# oneButton.net
KiCad netlist of a schematic drawn in Altium Designer
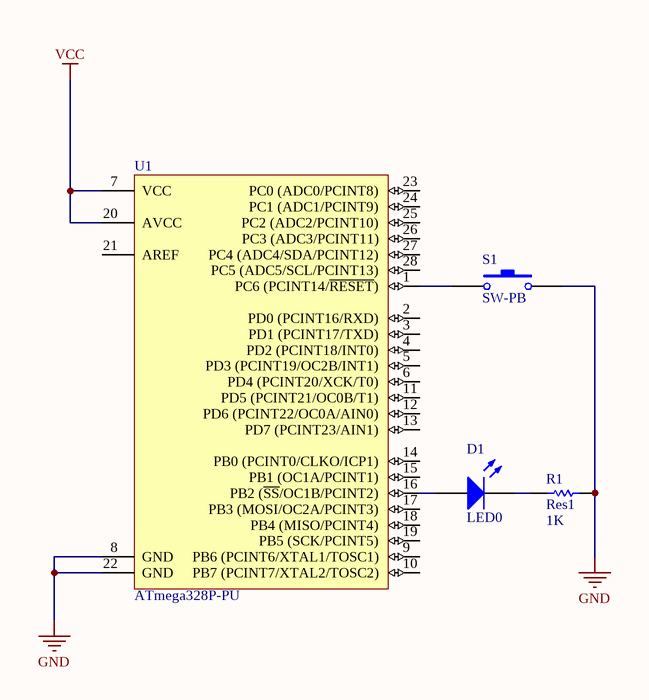
[diagram p0: oneButton.SchDoc]

(export (version "E")
  (design (tool "Eeschema 10.0.6"))
  (components
    (comp (ref "D1")
      (value "LED0")
      (footprint "LED-0")
      (description "Typical INFRARED GaAs LED")
      (fields (field (name "PUBLISHER") "Altium Limited"))
      (libsource (lib "Miscellaneous Devices") (part "LED0"))
    )
    (comp (ref "R1")
      (value "Res1")
      (footprint "AXIAL-0.3")
      (description "Resistor")
      (fields (field (name "ALTIUM_VALUE") "1K") (field (name "PUBLISHER") "Altium Limited"))
      (libsource (lib "Miscellaneous Devices") (part "Res1"))
    )
    (comp (ref "S1")
      (value "SW-PB")
      (footprint "SPST-2")
      (description "Switch")
      (fields (field (name "PUBLISHER") "Altium Limited"))
      (libsource (lib "Miscellaneous Devices") (part "SW-PB"))
    )
    (comp (ref "U1")
      (value "ATmega328P-PU")
      (footprint "28P3")
      (fields (field (name "PUBLISHER") "Altium Limited"))
      (libsource (lib "Atmel Microcontroller 8-Bit megaAVR") (part "ATmega328P-PU"))
    )
  )
  (nets
    (net (code "1") (name "GND") (class "Default")
      (node (ref "R1") (pin "2") (pinfunction "2_2") (pintype "passive"))
      (node (ref "S1") (pin "2") (pinfunction "2_2") (pintype "passive"))
      (node (ref "U1") (pin "22") (pinfunction "GND_22") (pintype "power_in"))
      (node (ref "U1") (pin "8") (pinfunction "GND_8") (pintype "power_in"))
    )
    (net (code "2") (name "Net-(D1-A)") (class "Default")
      (node (ref "D1") (pin "1") (pinfunction "A_1") (pintype "passive"))
      (node (ref "U1") (pin "16") (pinfunction "PB2_(~{SS}/OC1B/PCINT2)_16") (pintype "bidirectional"))
    )
    (net (code "3") (name "Net-(D1-K)") (class "Default")
      (node (ref "D1") (pin "2") (pinfunction "K_2") (pintype "passive"))
      (node (ref "R1") (pin "1") (pinfunction "1_1") (pintype "passive"))
    )
    (net (code "4") (name "Net-(U1-PC6_(PCINT14{slash}~{RESET}))") (class "Default")
      (node (ref "S1") (pin "1") (pinfunction "1_1") (pintype "passive"))
      (node (ref "U1") (pin "1") (pinfunction "PC6_(PCINT14/~{RESET})_1") (pintype "bidirectional"))
    )
    (net (code "5") (name "VCC") (class "Default")
      (node (ref "U1") (pin "20") (pinfunction "AVCC_20") (pintype "power_in"))
      (node (ref "U1") (pin "7") (pinfunction "VCC_7") (pintype "power_in"))
    )
    (net (code "6") (name "unconnected-(U1-AREF-Pad21)") (class "Default")
      (node (ref "U1") (pin "21") (pinfunction "AREF_21") (pintype "power_in"))
    )
    (net (code "7") (name "unconnected-(U1-PB0_(PCINT0{slash}CLKO{slash}ICP1)-Pad14)") (class "Default")
      (node (ref "U1") (pin "14") (pinfunction "PB0_(PCINT0/CLKO/ICP1)_14") (pintype "bidirectional"))
    )
    (net (code "8") (name "unconnected-(U1-PB1_(OC1A{slash}PCINT1)-Pad15)") (class "Default")
      (node (ref "U1") (pin "15") (pinfunction "PB1_(OC1A/PCINT1)_15") (pintype "bidirectional"))
    )
    (net (code "9") (name "unconnected-(U1-PB3_(MOSI{slash}OC2A{slash}PCINT3)-Pad17)") (class "Default")
      (node (ref "U1") (pin "17") (pinfunction "PB3_(MOSI/OC2A/PCINT3)_17") (pintype "bidirectional"))
    )
    (net (code "10") (name "unconnected-(U1-PB4_(MISO{slash}PCINT4)-Pad18)") (class "Default")
      (node (ref "U1") (pin "18") (pinfunction "PB4_(MISO/PCINT4)_18") (pintype "bidirectional"))
    )
    (net (code "11") (name "unconnected-(U1-PB5_(SCK{slash}PCINT5)-Pad19)") (class "Default")
      (node (ref "U1") (pin "19") (pinfunction "PB5_(SCK/PCINT5)_19") (pintype "bidirectional"))
    )
    (net (code "12") (name "unconnected-(U1-PB6_(PCINT6{slash}XTAL1{slash}TOSC1)-Pad9)") (class "Default")
      (node (ref "U1") (pin "9") (pinfunction "PB6_(PCINT6/XTAL1/TOSC1)_9") (pintype "bidirectional"))
    )
    (net (code "13") (name "unconnected-(U1-PB7_(PCINT7{slash}XTAL2{slash}TOSC2)-Pad10)") (class "Default")
      (node (ref "U1") (pin "10") (pinfunction "PB7_(PCINT7/XTAL2/TOSC2)_10") (pintype "bidirectional"))
    )
    (net (code "14") (name "unconnected-(U1-PC0_(ADC0{slash}PCINT8)-Pad23)") (class "Default")
      (node (ref "U1") (pin "23") (pinfunction "PC0_(ADC0/PCINT8)_23") (pintype "bidirectional"))
    )
    (net (code "15") (name "unconnected-(U1-PC1_(ADC1{slash}PCINT9)-Pad24)") (class "Default")
      (node (ref "U1") (pin "24") (pinfunction "PC1_(ADC1/PCINT9)_24") (pintype "bidirectional"))
    )
    (net (code "16") (name "unconnected-(U1-PC2_(ADC2{slash}PCINT10)-Pad25)") (class "Default")
      (node (ref "U1") (pin "25") (pinfunction "PC2_(ADC2/PCINT10)_25") (pintype "bidirectional"))
    )
    (net (code "17") (name "unconnected-(U1-PC3_(ADC3{slash}PCINT11)-Pad26)") (class "Default")
      (node (ref "U1") (pin "26") (pinfunction "PC3_(ADC3/PCINT11)_26") (pintype "bidirectional"))
    )
    (net (code "18") (name "unconnected-(U1-PC4_(ADC4{slash}SDA{slash}PCINT12)-Pad27)") (class "Default")
      (node (ref "U1") (pin "27") (pinfunction "PC4_(ADC4/SDA/PCINT12)_27") (pintype "bidirectional"))
    )
    (net (code "19") (name "unconnected-(U1-PC5_(ADC5{slash}SCL{slash}PCINT13)-Pad28)") (class "Default")
      (node (ref "U1") (pin "28") (pinfunction "PC5_(ADC5/SCL/PCINT13)_28") (pintype "bidirectional"))
    )
    (net (code "20") (name "unconnected-(U1-PD0_(PCINT16{slash}RXD)-Pad2)") (class "Default")
      (node (ref "U1") (pin "2") (pinfunction "PD0_(PCINT16/RXD)_2") (pintype "bidirectional"))
    )
    (net (code "21") (name "unconnected-(U1-PD1_(PCINT17{slash}TXD)-Pad3)") (class "Default")
      (node (ref "U1") (pin "3") (pinfunction "PD1_(PCINT17/TXD)_3") (pintype "bidirectional"))
    )
    (net (code "22") (name "unconnected-(U1-PD2_(PCINT18{slash}INT0)-Pad4)") (class "Default")
      (node (ref "U1") (pin "4") (pinfunction "PD2_(PCINT18/INT0)_4") (pintype "bidirectional"))
    )
    (net (code "23") (name "unconnected-(U1-PD3_(PCINT19{slash}OC2B{slash}INT1)-Pad5)") (class "Default")
      (node (ref "U1") (pin "5") (pinfunction "PD3_(PCINT19/OC2B/INT1)_5") (pintype "bidirectional"))
    )
    (net (code "24") (name "unconnected-(U1-PD4_(PCINT20{slash}XCK{slash}T0)-Pad6)") (class "Default")
      (node (ref "U1") (pin "6") (pinfunction "PD4_(PCINT20/XCK/T0)_6") (pintype "bidirectional"))
    )
    (net (code "25") (name "unconnected-(U1-PD5_(PCINT21{slash}OC0B{slash}T1)-Pad11)") (class "Default")
      (node (ref "U1") (pin "11") (pinfunction "PD5_(PCINT21/OC0B/T1)_11") (pintype "bidirectional"))
    )
    (net (code "26") (name "unconnected-(U1-PD6_(PCINT22{slash}OC0A{slash}AIN0)-Pad12)") (class "Default")
      (node (ref "U1") (pin "12") (pinfunction "PD6_(PCINT22/OC0A/AIN0)_12") (pintype "bidirectional"))
    )
    (net (code "27") (name "unconnected-(U1-PD7_(PCINT23{slash}AIN1)-Pad13)") (class "Default")
      (node (ref "U1") (pin "13") (pinfunction "PD7_(PCINT23/AIN1)_13") (pintype "bidirectional"))
    )
  )
)
